# Connectors.net
KiCad netlist of a schematic drawn in Altium Designer
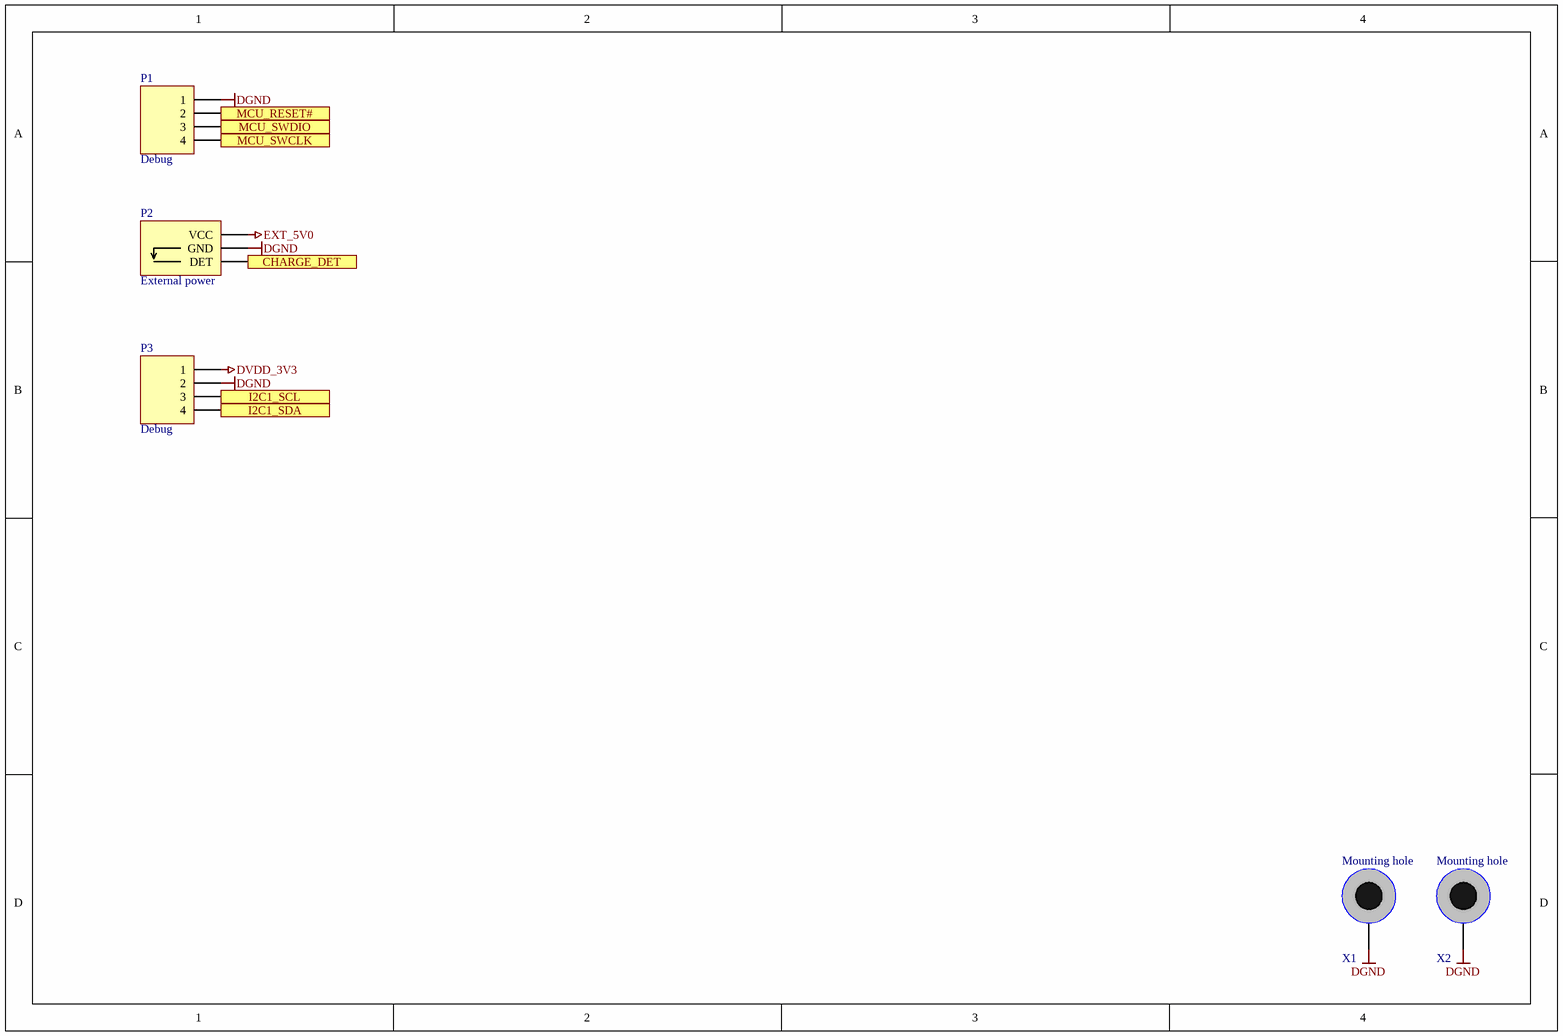
[diagram p0: Connectors.SchDoc]

(export (version "E")
  (design (tool "Eeschema 10.0.6"))
  (components
    (comp (ref "P1")
      (value "Debug")
      (footprint "PLS-4 2.54")
      (description "Header, 4-Pin")
      (fields (field (name "PUBLISHER") "Altium Limited"))
      (libsource (lib "connectors") (part "Header 4"))
    )
    (comp (ref "P2")
      (value "External power")
      (footprint "DC-210")
      (description "Power connector 3.5mm")
      (fields (field (name "PUBLISHER") "Altium Limited"))
      (libsource (lib "connectors") (part "DC-210"))
    )
    (comp (ref "P3")
      (value "Debug")
      (footprint "PLS-4 2.54")
      (description "Header, 4-Pin")
      (fields (field (name "PUBLISHER") "Altium Limited"))
      (libsource (lib "connectors") (part "Header 4"))
    )
    (comp (ref "X1")
      (value "Mounting hole")
      (footprint "HOLE_M2_D4.0/2.5")
      (description "Hole for screw M3, outline D6")
      (libsource (lib "connectors") (part "Mounting hole"))
    )
    (comp (ref "X2")
      (value "Mounting hole")
      (footprint "HOLE_M2_D4.0/2.5")
      (description "Hole for screw M3, outline D6")
      (libsource (lib "connectors") (part "Mounting hole"))
    )
  )
  (nets
    (net (code "1") (name "/CHARGE_DET") (class "Default")
      (node (ref "P2") (pin "3") (pinfunction "DET_3") (pintype "passive"))
    )
    (net (code "2") (name "/I2C1_SCL") (class "Default")
      (node (ref "P3") (pin "3") (pinfunction "3_3") (pintype "passive"))
    )
    (net (code "3") (name "/I2C1_SDA") (class "Default")
      (node (ref "P3") (pin "4") (pinfunction "4_4") (pintype "passive"))
    )
    (net (code "4") (name "/MCU_RESET#") (class "Default")
      (node (ref "P1") (pin "2") (pinfunction "2_2") (pintype "passive"))
    )
    (net (code "5") (name "/MCU_SWCLK") (class "Default")
      (node (ref "P1") (pin "4") (pinfunction "4_4") (pintype "passive"))
    )
    (net (code "6") (name "/MCU_SWDIO") (class "Default")
      (node (ref "P1") (pin "3") (pinfunction "3_3") (pintype "passive"))
    )
    (net (code "7") (name "DGND") (class "Default")
      (node (ref "P1") (pin "1") (pinfunction "1_1") (pintype "passive"))
      (node (ref "P2") (pin "2") (pinfunction "GND_2") (pintype "passive"))
      (node (ref "P3") (pin "2") (pinfunction "2_2") (pintype "passive"))
      (node (ref "X1") (pin "1") (pintype "passive"))
      (node (ref "X2") (pin "1") (pintype "passive"))
    )
    (net (code "8") (name "DVDD_3V3") (class "Default")
      (node (ref "P3") (pin "1") (pinfunction "1_1") (pintype "passive"))
    )
    (net (code "9") (name "EXT_5V0") (class "Default")
      (node (ref "P2") (pin "1") (pinfunction "VCC_1") (pintype "passive"))
    )
  )
)
